# 02-Power_Supply.net
KiCad netlist of a schematic drawn in Altium Designer
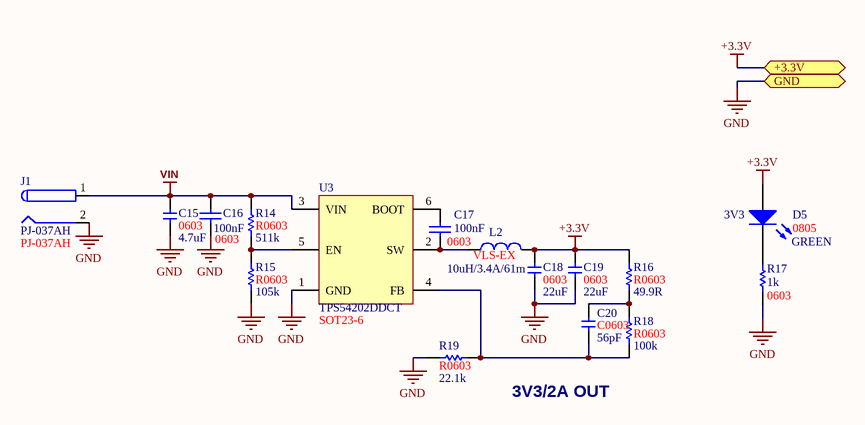
[diagram p0: 02-Power_Supply.SchDoc]

(export (version "E")
  (design (tool "Eeschema 10.0.6"))
  (components
    (comp (ref "C15")
      (value "4.7uF")
      (footprint "C0603")
      (description "Capacitor")
      (fields
        (field (name "MANUFACTURER PART NUMBER") "C1608X5R1C475M080AC")
        (field (name "PACKAGEREFERENCE") "0603")
      )
      (libsource (lib "schematic_library") (part "Cap_0603"))
    )
    (comp (ref "C16")
      (value "100nF")
      (footprint "C0603")
      (description "Capacitor (Semiconductor SIM Model)")
      (fields
        (field (name "MANUFACTURER PART NUMBER") "CL10F104ZO8NNNC")
        (field (name "PACKAGEREFERENCE") "0603")
      )
      (libsource (lib "Miscellaneous Devices") (part "Cap Semi"))
    )
    (comp (ref "C17")
      (value "100nF")
      (footprint "C0603")
      (description "Capacitor (Semiconductor SIM Model)")
      (fields
        (field (name "MANUFACTURER PART NUMBER") "CL10F104ZO8NNNC")
        (field (name "PACKAGEREFERENCE") "0603")
      )
      (libsource (lib "Miscellaneous Devices") (part "Cap Semi"))
    )
    (comp (ref "C18")
      (value "22uF")
      (footprint "C0603")
      (description "Capacitor")
      (fields
        (field (name "MANUFACTURER PART NUMBER") "CL10A226MQ8NRNC")
        (field (name "PACKAGEREFERENCE") "0603")
      )
      (libsource (lib "schematic_library") (part "Cap_0603"))
    )
    (comp (ref "C19")
      (value "22uF")
      (footprint "C0603")
      (description "Capacitor")
      (fields
        (field (name "MANUFACTURER PART NUMBER") "CL10A226MQ8NRNC")
        (field (name "PACKAGEREFERENCE") "0603")
      )
      (libsource (lib "schematic_library") (part "Cap_0603"))
    )
    (comp (ref "C20")
      (value "56pF")
      (footprint "C0603")
      (description "Capacitor")
      (fields
        (field (name "MANUFACTURER PART NUMBER") "CL10C560JB8NNNC")
        (field (name "PACKAGEREFERENCE") "C0603")
      )
      (libsource (lib "schematic_library") (part "Cap_0402"))
    )
    (comp (ref "D5")
      (value "3V3")
      (footprint "LED0805")
      (description "GREEN")
      (fields
        (field (name "PACKAGEREFERENCE") "0805")
        (field (name "ALTIUM_VALUE") "GREEN")
        (field (name "MANUFACTURER PART NUMBER") "LTST-S220GKT")
      )
      (libsource (lib "Library_Scott") (part "LED_SMD"))
    )
    (comp (ref "J1")
      (value "PJ-037AH")
      (footprint "CON_PJ-037A")
      (description "CONN PWR JACK 2X5.5MM SOLDER")
      (fields (field (name "PACKAGEREFERENCE") "PJ-037AH"))
      (libsource (lib "schematic_library") (part "PJ-037AH"))
    )
    (comp (ref "L2")
      (value "10uH/3.4A/61m")
      (footprint "IND6045")
      (description "Inductor")
      (fields
        (field (name "MANUFACTURER PART NUMBER") "VLS6045EX-100M")
        (field (name "PACKAGEREFERENCE") "VLS-EX")
      )
      (libsource (lib "schematic_library") (part "Inductor_0603"))
    )
    (comp (ref "R14")
      (value "511k")
      (footprint "R0603")
      (description "Resistor")
      (fields
        (field (name "MANUFACTURER PART NUMBER") "RMCF0603FT511K")
        (field (name "PACKAGEREFERENCE") "R0603")
      )
      (libsource (lib "schematic_library") (part "Res_0402"))
    )
    (comp (ref "R15")
      (value "105k")
      (footprint "R0603")
      (description "Resistor")
      (fields
        (field (name "MANUFACTURER PART NUMBER") "RMCF0603FT105K")
        (field (name "PACKAGEREFERENCE") "R0603")
      )
      (libsource (lib "schematic_library") (part "Res_0402"))
    )
    (comp (ref "R16")
      (value "49.9R")
      (footprint "R0603")
      (description "Resistor")
      (fields
        (field (name "MANUFACTURER PART NUMBER") "RMCF0603FT49R9")
        (field (name "PACKAGEREFERENCE") "R0603")
      )
      (libsource (lib "schematic_library") (part "Res_0402"))
    )
    (comp (ref "R17")
      (value "1k")
      (footprint "R0603")
      (description "Resistor")
      (fields
        (field (name "MANUFACTURER PART NUMBER") "RMCF0603FG1K00")
        (field (name "PACKAGEREFERENCE") "0603")
      )
      (libsource (lib "Miscellaneous Devices") (part "Res1"))
    )
    (comp (ref "R18")
      (value "100k")
      (footprint "R0603")
      (description "Resistor")
      (fields
        (field (name "MANUFACTURER PART NUMBER") "CR0603-JW-104ELF")
        (field (name "PACKAGEREFERENCE") "R0603")
      )
      (libsource (lib "schematic_library") (part "Res_0402"))
    )
    (comp (ref "R19")
      (value "22.1k")
      (footprint "R0603")
      (description "Resistor")
      (fields
        (field (name "MANUFACTURER PART NUMBER") "RNCP0603FTD22K1")
        (field (name "PACKAGEREFERENCE") "R0603")
      )
      (libsource (lib "schematic_library") (part "Res_0402"))
    )
    (comp (ref "U3")
      (value "TPS54202DDCT")
      (footprint "SOT23-6")
      (description "IC REG BUCK ADJ 2A SYNC SOT23-6")
      (fields (field (name "PACKAGEREFERENCE") "SOT23-6"))
      (libsource (lib "schematic_library") (part "TPS54202DDCT"))
    )
  )
  (nets
    (net (code "1") (name "+3.3V") (class "Default")
      (node (ref "C18") (pin "2") (pinfunction "2_2") (pintype "passive"))
      (node (ref "C19") (pin "2") (pinfunction "2_2") (pintype "passive"))
      (node (ref "D5") (pin "1") (pinfunction "A_1") (pintype "passive"))
      (node (ref "L2") (pin "2") (pinfunction "2_2") (pintype "passive"))
      (node (ref "R16") (pin "1") (pinfunction "1_1") (pintype "passive"))
    )
    (net (code "2") (name "GND") (class "Default")
      (node (ref "C15") (pin "1") (pinfunction "1_1") (pintype "passive"))
      (node (ref "C16") (pin "1") (pinfunction "1_1") (pintype "passive"))
      (node (ref "C18") (pin "1") (pinfunction "1_1") (pintype "passive"))
      (node (ref "C19") (pin "1") (pinfunction "1_1") (pintype "passive"))
      (node (ref "J1") (pin "2") (pinfunction "2_2") (pintype "power_in"))
      (node (ref "R15") (pin "2") (pinfunction "2_2") (pintype "passive"))
      (node (ref "R17") (pin "1") (pinfunction "1_1") (pintype "passive"))
      (node (ref "R19") (pin "1") (pinfunction "1_1") (pintype "passive"))
      (node (ref "U3") (pin "1") (pinfunction "GND_1") (pintype "passive"))
    )
    (net (code "3") (name "Net-(C20-Pad2)") (class "Default")
      (node (ref "C20") (pin "2") (pinfunction "2_2") (pintype "passive"))
      (node (ref "R16") (pin "2") (pinfunction "2_2") (pintype "passive"))
      (node (ref "R18") (pin "1") (pinfunction "1_1") (pintype "passive"))
    )
    (net (code "4") (name "Net-(D5-K)") (class "Default")
      (node (ref "D5") (pin "2") (pinfunction "K_2") (pintype "passive"))
      (node (ref "R17") (pin "2") (pinfunction "2_2") (pintype "passive"))
    )
    (net (code "5") (name "Net-(U3-BOOT)") (class "Default")
      (node (ref "C17") (pin "2") (pinfunction "2_2") (pintype "passive"))
      (node (ref "U3") (pin "6") (pinfunction "BOOT_6") (pintype "passive"))
    )
    (net (code "6") (name "Net-(U3-EN)") (class "Default")
      (node (ref "R14") (pin "2") (pinfunction "2_2") (pintype "passive"))
      (node (ref "R15") (pin "1") (pinfunction "1_1") (pintype "passive"))
      (node (ref "U3") (pin "5") (pinfunction "EN_5") (pintype "passive"))
    )
    (net (code "7") (name "Net-(U3-FB)") (class "Default")
      (node (ref "C20") (pin "1") (pinfunction "1_1") (pintype "passive"))
      (node (ref "R18") (pin "2") (pinfunction "2_2") (pintype "passive"))
      (node (ref "R19") (pin "2") (pinfunction "2_2") (pintype "passive"))
      (node (ref "U3") (pin "4") (pinfunction "FB_4") (pintype "passive"))
    )
    (net (code "8") (name "Net-(U3-SW)") (class "Default")
      (node (ref "C17") (pin "1") (pinfunction "1_1") (pintype "passive"))
      (node (ref "L2") (pin "1") (pinfunction "1_1") (pintype "passive"))
      (node (ref "U3") (pin "2") (pinfunction "SW_2") (pintype "passive"))
    )
    (net (code "9") (name "VIN") (class "Default")
      (node (ref "C15") (pin "2") (pinfunction "2_2") (pintype "passive"))
      (node (ref "C16") (pin "2") (pinfunction "2_2") (pintype "passive"))
      (node (ref "J1") (pin "1") (pinfunction "1_1") (pintype "power_in"))
      (node (ref "R14") (pin "1") (pinfunction "1_1") (pintype "passive"))
      (node (ref "U3") (pin "3") (pinfunction "VIN_3") (pintype "passive"))
    )
  )
)
